# mainv5.net
KiCad netlist of a schematic drawn in EAGLE
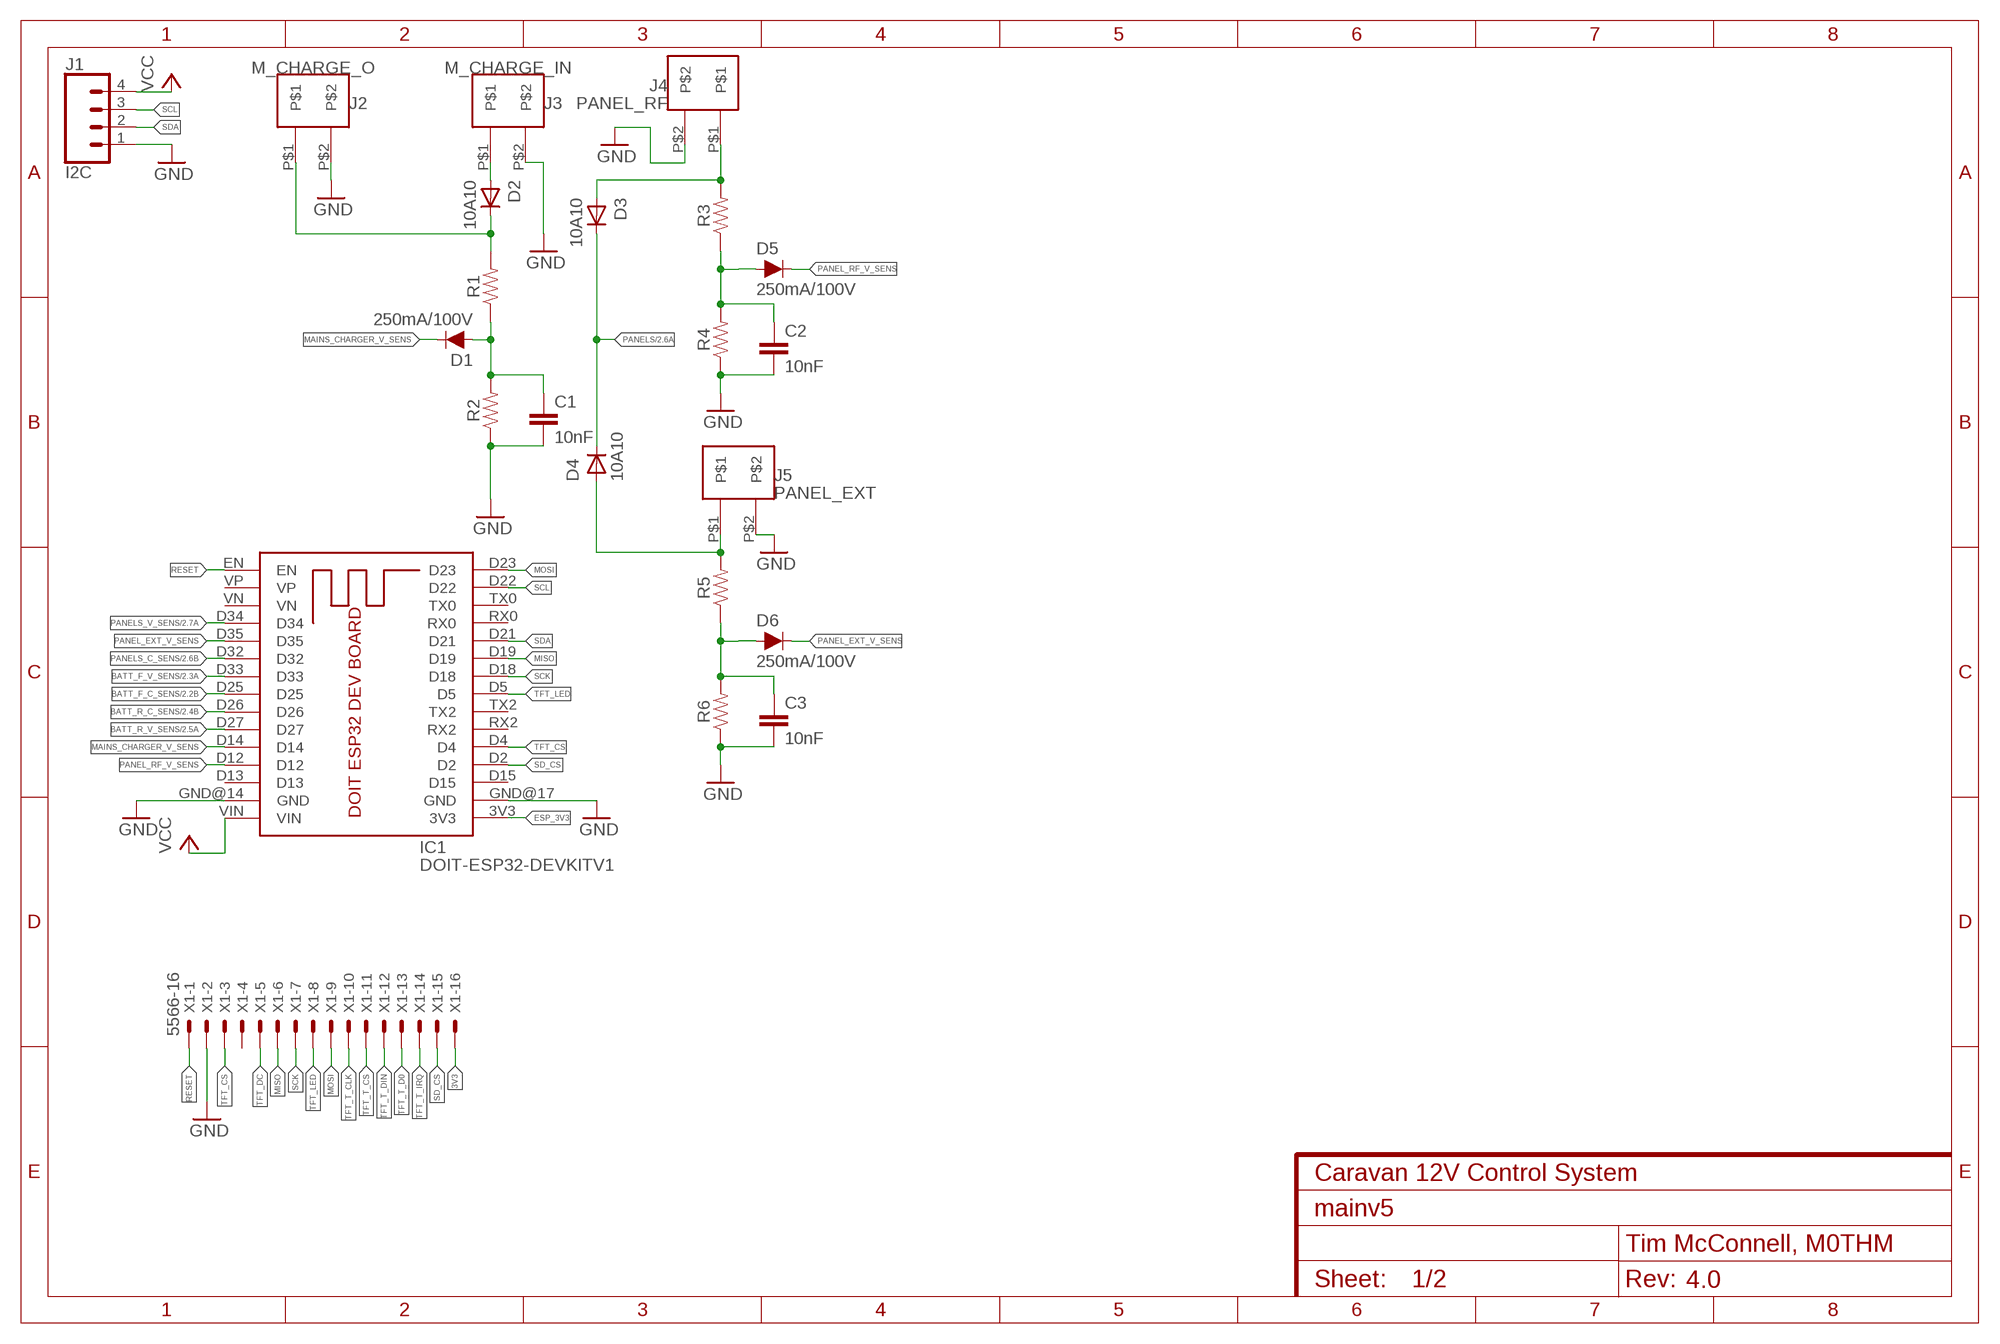
[diagram p0: schematic, sheet 1]
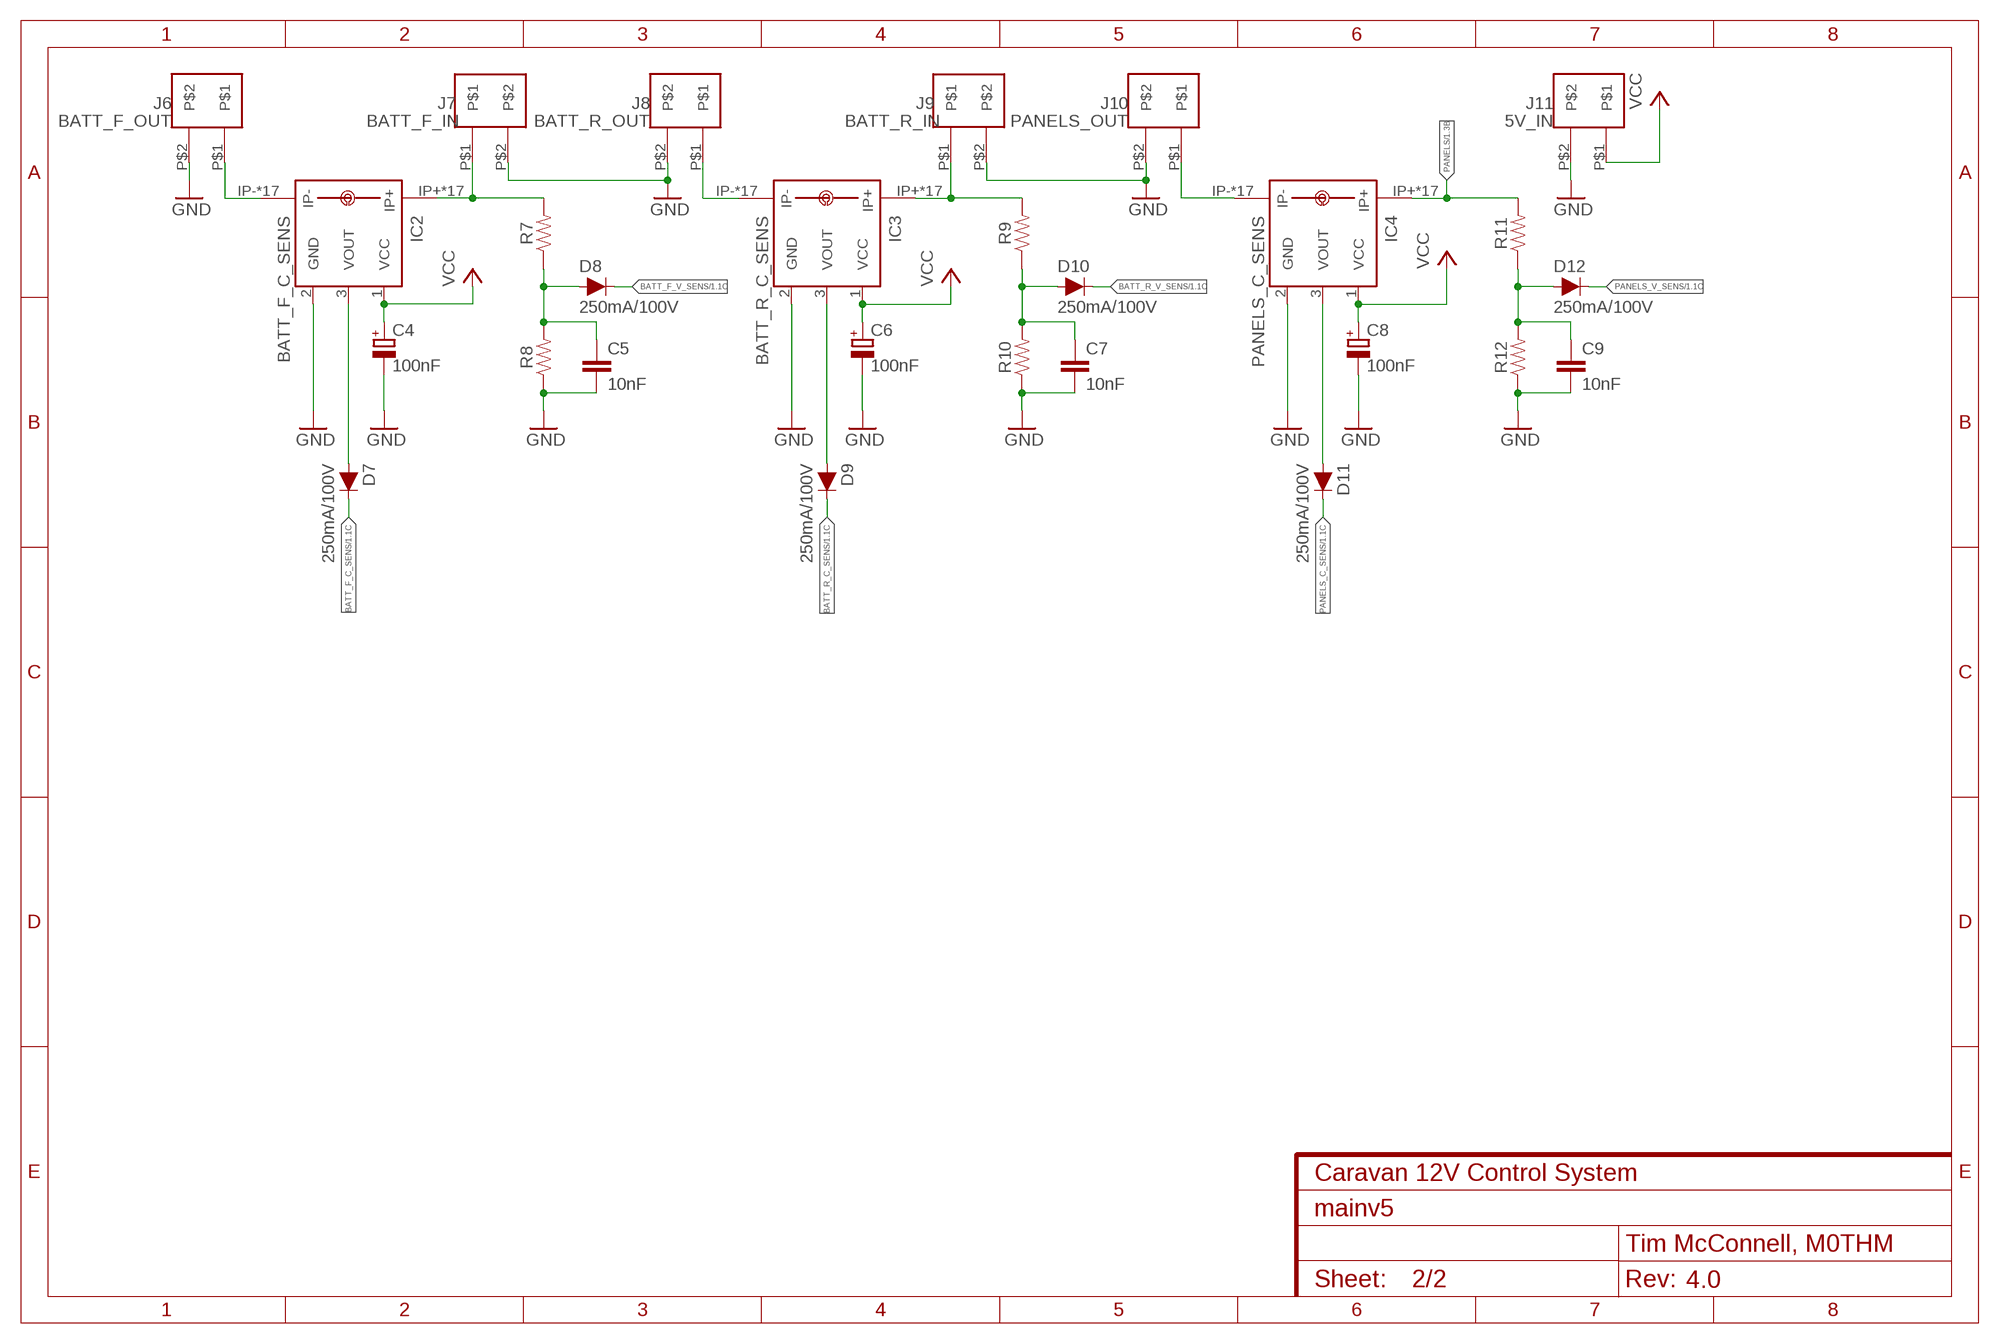
[diagram p1: schematic, sheet 2]

(export (version "E")
  (design (tool "Eeschema 10.0.6"))
  (components
    (comp (ref "C4")
      (value "100nF")
      (footprint "eagle-import:PANASONIC_E")
      (libsource (lib "eagle-import") (part "CPOL-EUE"))
    )
    (comp (ref "C5")
      (value "10nF")
      (footprint "eagle-import:0603")
      (libsource (lib "eagle-import") (part "10NF-0603-50V-10%"))
    )
    (comp (ref "C6")
      (value "100nF")
      (footprint "eagle-import:PANASONIC_E")
      (libsource (lib "eagle-import") (part "CPOL-EUE"))
    )
    (comp (ref "C7")
      (value "10nF")
      (footprint "eagle-import:0603")
      (libsource (lib "eagle-import") (part "10NF-0603-50V-10%"))
    )
    (comp (ref "C8")
      (value "100nF")
      (footprint "eagle-import:PANASONIC_E")
      (libsource (lib "eagle-import") (part "CPOL-EUE"))
    )
    (comp (ref "C9")
      (value "10nF")
      (footprint "eagle-import:0603")
      (libsource (lib "eagle-import") (part "10NF-0603-50V-10%"))
    )
    (comp (ref "D7")
      (value "250mA/100V")
      (footprint "eagle-import:SOD-323")
      (libsource (lib "eagle-import") (part "DIODE-BAS16J"))
    )
    (comp (ref "D8")
      (value "250mA/100V")
      (footprint "eagle-import:SOD-323")
      (libsource (lib "eagle-import") (part "DIODE-BAS16J"))
    )
    (comp (ref "D9")
      (value "250mA/100V")
      (footprint "eagle-import:SOD-323")
      (libsource (lib "eagle-import") (part "DIODE-BAS16J"))
    )
    (comp (ref "D10")
      (value "250mA/100V")
      (footprint "eagle-import:SOD-323")
      (libsource (lib "eagle-import") (part "DIODE-BAS16J"))
    )
    (comp (ref "D11")
      (value "250mA/100V")
      (footprint "eagle-import:SOD-323")
      (libsource (lib "eagle-import") (part "DIODE-BAS16J"))
    )
    (comp (ref "D12")
      (value "250mA/100V")
      (footprint "eagle-import:SOD-323")
      (libsource (lib "eagle-import") (part "DIODE-BAS16J"))
    )
    (comp (ref "IC2")
      (value "BATT_F_C_SENS")
      (footprint "eagle-import:CB-PFF")
      (fields (field (name "MPN") "ACS758ECB-200B-PFF-T"))
      (libsource (lib "eagle-import") (part "ACS758ECB-200B-PFF-T"))
    )
    (comp (ref "IC3")
      (value "BATT_R_C_SENS")
      (footprint "eagle-import:CB-PFF")
      (fields (field (name "MPN") "ACS758ECB-200B-PFF-T"))
      (libsource (lib "eagle-import") (part "ACS758ECB-200B-PFF-T"))
    )
    (comp (ref "IC4")
      (value "PANELS_C_SENS")
      (footprint "eagle-import:CB-PFF")
      (fields (field (name "MPN") "ACS758ECB-200B-PFF-T"))
      (libsource (lib "eagle-import") (part "ACS758ECB-200B-PFF-T"))
    )
    (comp (ref "J6")
      (value "BATT_F_OUT")
      (footprint "eagle-import:40A-2PIN")
      (libsource (lib "eagle-import") (part "40A-2PIN"))
    )
    (comp (ref "J7")
      (value "BATT_F_IN")
      (footprint "eagle-import:40A-2PIN")
      (libsource (lib "eagle-import") (part "40A-2PIN"))
    )
    (comp (ref "J8")
      (value "BATT_R_OUT")
      (footprint "eagle-import:40A-2PIN")
      (libsource (lib "eagle-import") (part "40A-2PIN"))
    )
    (comp (ref "J9")
      (value "BATT_R_IN")
      (footprint "eagle-import:40A-2PIN")
      (libsource (lib "eagle-import") (part "40A-2PIN"))
    )
    (comp (ref "J10")
      (value "PANELS_OUT")
      (footprint "eagle-import:40A-2PIN")
      (libsource (lib "eagle-import") (part "40A-2PIN"))
    )
    (comp (ref "J11")
      (value "5V_IN")
      (footprint "eagle-import:40A-2PIN")
      (libsource (lib "eagle-import") (part "40A-2PIN"))
    )
    (comp (ref "R7")
      (value "RESISTOR0805")
      (footprint "eagle-import:0805")
      (libsource (lib "eagle-import") (part "RESISTOR0805"))
    )
    (comp (ref "R8")
      (value "RESISTOR0805")
      (footprint "eagle-import:0805")
      (libsource (lib "eagle-import") (part "RESISTOR0805"))
    )
    (comp (ref "R9")
      (value "RESISTOR0805")
      (footprint "eagle-import:0805")
      (libsource (lib "eagle-import") (part "RESISTOR0805"))
    )
    (comp (ref "R10")
      (value "RESISTOR0805")
      (footprint "eagle-import:0805")
      (libsource (lib "eagle-import") (part "RESISTOR0805"))
    )
    (comp (ref "R11")
      (value "RESISTOR0805")
      (footprint "eagle-import:0805")
      (libsource (lib "eagle-import") (part "RESISTOR0805"))
    )
    (comp (ref "R12")
      (value "RESISTOR0805")
      (footprint "eagle-import:0805")
      (libsource (lib "eagle-import") (part "RESISTOR0805"))
    )
    (comp (ref "C1")
      (value "10nF")
      (footprint "eagle-import:0603")
      (libsource (lib "eagle-import") (part "10NF-0603-50V-10%"))
    )
    (comp (ref "C2")
      (value "10nF")
      (footprint "eagle-import:0603")
      (libsource (lib "eagle-import") (part "10NF-0603-50V-10%"))
    )
    (comp (ref "C3")
      (value "10nF")
      (footprint "eagle-import:0603")
      (libsource (lib "eagle-import") (part "10NF-0603-50V-10%"))
    )
    (comp (ref "D1")
      (value "250mA/100V")
      (footprint "eagle-import:SOD-323")
      (libsource (lib "eagle-import") (part "DIODE-BAS16J"))
    )
    (comp (ref "D2")
      (value "10A10")
      (footprint "eagle-import:AG")
      (libsource (lib "eagle-import") (part "10A10"))
    )
    (comp (ref "D3")
      (value "10A10")
      (footprint "eagle-import:AG")
      (libsource (lib "eagle-import") (part "10A10"))
    )
    (comp (ref "D4")
      (value "10A10")
      (footprint "eagle-import:AG")
      (libsource (lib "eagle-import") (part "10A10"))
    )
    (comp (ref "D5")
      (value "250mA/100V")
      (footprint "eagle-import:SOD-323")
      (libsource (lib "eagle-import") (part "DIODE-BAS16J"))
    )
    (comp (ref "D6")
      (value "250mA/100V")
      (footprint "eagle-import:SOD-323")
      (libsource (lib "eagle-import") (part "DIODE-BAS16J"))
    )
    (comp (ref "IC1")
      (value "DOIT-ESP32-DEVKITV1")
      (footprint "eagle-import:DOIT-ESP32-DEVKITV1")
      (libsource (lib "eagle-import") (part "DOIT-ESP32-DEVKITV1"))
    )
    (comp (ref "J1")
      (value "I2C")
      (footprint "eagle-import:MOLEX-1X4")
      (libsource (lib "eagle-import") (part "CONN_04POLAR"))
    )
    (comp (ref "J2")
      (value "M_CHARGE_O")
      (footprint "eagle-import:40A-2PIN")
      (libsource (lib "eagle-import") (part "40A-2PIN"))
    )
    (comp (ref "J3")
      (value "M_CHARGE_IN")
      (footprint "eagle-import:40A-2PIN")
      (libsource (lib "eagle-import") (part "40A-2PIN"))
    )
    (comp (ref "J4")
      (value "PANEL_RF")
      (footprint "eagle-import:40A-2PIN")
      (libsource (lib "eagle-import") (part "40A-2PIN"))
    )
    (comp (ref "J5")
      (value "PANEL_EXT")
      (footprint "eagle-import:40A-2PIN")
      (libsource (lib "eagle-import") (part "40A-2PIN"))
    )
    (comp (ref "R1")
      (value "RESISTOR0805")
      (footprint "eagle-import:0805")
      (libsource (lib "eagle-import") (part "RESISTOR0805"))
    )
    (comp (ref "R2")
      (value "RESISTOR0805")
      (footprint "eagle-import:0805")
      (libsource (lib "eagle-import") (part "RESISTOR0805"))
    )
    (comp (ref "R3")
      (value "RESISTOR0805")
      (footprint "eagle-import:0805")
      (libsource (lib "eagle-import") (part "RESISTOR0805"))
    )
    (comp (ref "R4")
      (value "RESISTOR0805")
      (footprint "eagle-import:0805")
      (libsource (lib "eagle-import") (part "RESISTOR0805"))
    )
    (comp (ref "R5")
      (value "RESISTOR0805")
      (footprint "eagle-import:0805")
      (libsource (lib "eagle-import") (part "RESISTOR0805"))
    )
    (comp (ref "R6")
      (value "RESISTOR0805")
      (footprint "eagle-import:0805")
      (libsource (lib "eagle-import") (part "RESISTOR0805"))
    )
    (comp (ref "X1")
      (value "5566-16")
      (footprint "eagle-import:5566-16")
      (fields (field (name "MF") "MOLEX"))
      (libsource (lib "eagle-import") (part "5566-16"))
    )
  )
  (nets
    (net (code "1") (name "3V3") (class "Default")
      (node (ref "X1") (pin "16") (pinfunction "S_16") (pintype "passive"))
    )
    (net (code "2") (name "BATT_F_C_SENS") (class "Default")
      (node (ref "D7") (pin "C") (pinfunction "C_C") (pintype "passive"))
      (node (ref "IC1") (pin "D25") (pinfunction "D25_D25") (pintype "bidirectional"))
    )
    (net (code "3") (name "BATT_F_V_SENS") (class "Default")
      (node (ref "D8") (pin "C") (pinfunction "C_C") (pintype "passive"))
      (node (ref "IC1") (pin "D33") (pinfunction "D33_D33") (pintype "bidirectional"))
    )
    (net (code "4") (name "BATT_R_C_SENS") (class "Default")
      (node (ref "D9") (pin "C") (pinfunction "C_C") (pintype "passive"))
      (node (ref "IC1") (pin "D26") (pinfunction "D26_D26") (pintype "bidirectional"))
    )
    (net (code "5") (name "BATT_R_V_SENS") (class "Default")
      (node (ref "D10") (pin "C") (pinfunction "C_C") (pintype "passive"))
      (node (ref "IC1") (pin "D27") (pinfunction "D27_D27") (pintype "bidirectional"))
    )
    (net (code "6") (name "ESP_3V3") (class "Default")
      (node (ref "IC1") (pin "3V3") (pinfunction "3V3_3V3") (pintype "power_in"))
    )
    (net (code "7") (name "GND") (class "Default")
      (node (ref "C1") (pin "2") (pinfunction "2_2") (pintype "passive"))
      (node (ref "C2") (pin "2") (pinfunction "2_2") (pintype "passive"))
      (node (ref "C3") (pin "2") (pinfunction "2_2") (pintype "passive"))
      (node (ref "C4") (pin "-") (pinfunction "-_-") (pintype "passive"))
      (node (ref "C5") (pin "2") (pinfunction "2_2") (pintype "passive"))
      (node (ref "C6") (pin "-") (pinfunction "-_-") (pintype "passive"))
      (node (ref "C7") (pin "2") (pinfunction "2_2") (pintype "passive"))
      (node (ref "C8") (pin "-") (pinfunction "-_-") (pintype "passive"))
      (node (ref "C9") (pin "2") (pinfunction "2_2") (pintype "passive"))
      (node (ref "IC1") (pin "GND@14") (pinfunction "GND_GND@14") (pintype "power_in"))
      (node (ref "IC1") (pin "GND@17") (pinfunction "GND_GND@17") (pintype "power_in"))
      (node (ref "IC2") (pin "2") (pinfunction "GND_2") (pintype "power_in"))
      (node (ref "IC3") (pin "2") (pinfunction "GND_2") (pintype "power_in"))
      (node (ref "IC4") (pin "2") (pinfunction "GND_2") (pintype "power_in"))
      (node (ref "J1") (pin "1") (pinfunction "1_1") (pintype "passive"))
      (node (ref "J10") (pin "P$2") (pinfunction "P$2_P$2") (pintype "bidirectional"))
      (node (ref "J11") (pin "P$2") (pinfunction "P$2_P$2") (pintype "bidirectional"))
      (node (ref "J2") (pin "P$2") (pinfunction "P$2_P$2") (pintype "bidirectional"))
      (node (ref "J3") (pin "P$2") (pinfunction "P$2_P$2") (pintype "bidirectional"))
      (node (ref "J4") (pin "P$2") (pinfunction "P$2_P$2") (pintype "bidirectional"))
      (node (ref "J5") (pin "P$2") (pinfunction "P$2_P$2") (pintype "bidirectional"))
      (node (ref "J6") (pin "P$2") (pinfunction "P$2_P$2") (pintype "bidirectional"))
      (node (ref "J7") (pin "P$2") (pinfunction "P$2_P$2") (pintype "bidirectional"))
      (node (ref "J8") (pin "P$2") (pinfunction "P$2_P$2") (pintype "bidirectional"))
      (node (ref "J9") (pin "P$2") (pinfunction "P$2_P$2") (pintype "bidirectional"))
      (node (ref "R10") (pin "1") (pinfunction "1_1") (pintype "passive"))
      (node (ref "R12") (pin "1") (pinfunction "1_1") (pintype "passive"))
      (node (ref "R2") (pin "1") (pinfunction "1_1") (pintype "passive"))
      (node (ref "R4") (pin "1") (pinfunction "1_1") (pintype "passive"))
      (node (ref "R6") (pin "1") (pinfunction "1_1") (pintype "passive"))
      (node (ref "R8") (pin "1") (pinfunction "1_1") (pintype "passive"))
      (node (ref "X1") (pin "2") (pinfunction "S_2") (pintype "passive"))
    )
    (net (code "8") (name "MAINS_CHARGER_V_SENS") (class "Default")
      (node (ref "D1") (pin "C") (pinfunction "C_C") (pintype "passive"))
      (node (ref "IC1") (pin "D14") (pinfunction "D14_D14") (pintype "bidirectional"))
    )
    (net (code "9") (name "MISO") (class "Default")
      (node (ref "IC1") (pin "D19") (pinfunction "D19_D19") (pintype "bidirectional"))
      (node (ref "X1") (pin "6") (pinfunction "S_6") (pintype "passive"))
    )
    (net (code "10") (name "MOSI") (class "Default")
      (node (ref "IC1") (pin "D23") (pinfunction "D23_D23") (pintype "bidirectional"))
      (node (ref "X1") (pin "9") (pinfunction "S_9") (pintype "passive"))
    )
    (net (code "11") (name "Net-(C1-Pad1)") (class "Default")
      (node (ref "C1") (pin "1") (pinfunction "1_1") (pintype "passive"))
      (node (ref "D1") (pin "A") (pinfunction "A_A") (pintype "passive"))
      (node (ref "R1") (pin "1") (pinfunction "1_1") (pintype "passive"))
      (node (ref "R2") (pin "2") (pinfunction "2_2") (pintype "passive"))
    )
    (net (code "12") (name "Net-(C2-Pad1)") (class "Default")
      (node (ref "C2") (pin "1") (pinfunction "1_1") (pintype "passive"))
      (node (ref "D5") (pin "A") (pinfunction "A_A") (pintype "passive"))
      (node (ref "R3") (pin "1") (pinfunction "1_1") (pintype "passive"))
      (node (ref "R4") (pin "2") (pinfunction "2_2") (pintype "passive"))
    )
    (net (code "13") (name "Net-(C3-Pad1)") (class "Default")
      (node (ref "C3") (pin "1") (pinfunction "1_1") (pintype "passive"))
      (node (ref "D6") (pin "A") (pinfunction "A_A") (pintype "passive"))
      (node (ref "R5") (pin "1") (pinfunction "1_1") (pintype "passive"))
      (node (ref "R6") (pin "2") (pinfunction "2_2") (pintype "passive"))
    )
    (net (code "14") (name "Net-(C5-Pad1)") (class "Default")
      (node (ref "C5") (pin "1") (pinfunction "1_1") (pintype "passive"))
      (node (ref "D8") (pin "A") (pinfunction "A_A") (pintype "passive"))
      (node (ref "R7") (pin "1") (pinfunction "1_1") (pintype "passive"))
      (node (ref "R8") (pin "2") (pinfunction "2_2") (pintype "passive"))
    )
    (net (code "15") (name "Net-(C7-Pad1)") (class "Default")
      (node (ref "C7") (pin "1") (pinfunction "1_1") (pintype "passive"))
      (node (ref "D10") (pin "A") (pinfunction "A_A") (pintype "passive"))
      (node (ref "R10") (pin "2") (pinfunction "2_2") (pintype "passive"))
      (node (ref "R9") (pin "1") (pinfunction "1_1") (pintype "passive"))
    )
    (net (code "16") (name "Net-(C9-Pad1)") (class "Default")
      (node (ref "C9") (pin "1") (pinfunction "1_1") (pintype "passive"))
      (node (ref "D12") (pin "A") (pinfunction "A_A") (pintype "passive"))
      (node (ref "R11") (pin "1") (pinfunction "1_1") (pintype "passive"))
      (node (ref "R12") (pin "2") (pinfunction "2_2") (pintype "passive"))
    )
    (net (code "17") (name "Net-(D2-PadA)") (class "Default")
      (node (ref "D2") (pin "A") (pinfunction "A_A") (pintype "passive"))
      (node (ref "J3") (pin "P$1") (pinfunction "P$1_P$1") (pintype "bidirectional"))
    )
    (net (code "18") (name "Net-(D2-PadC)") (class "Default")
      (node (ref "D2") (pin "C") (pinfunction "C_C") (pintype "passive"))
      (node (ref "J2") (pin "P$1") (pinfunction "P$1_P$1") (pintype "bidirectional"))
      (node (ref "R1") (pin "2") (pinfunction "2_2") (pintype "passive"))
    )
    (net (code "19") (name "Net-(D3-PadA)") (class "Default")
      (node (ref "D3") (pin "A") (pinfunction "A_A") (pintype "passive"))
      (node (ref "J4") (pin "P$1") (pinfunction "P$1_P$1") (pintype "bidirectional"))
      (node (ref "R3") (pin "2") (pinfunction "2_2") (pintype "passive"))
    )
    (net (code "20") (name "Net-(D4-PadA)") (class "Default")
      (node (ref "D4") (pin "A") (pinfunction "A_A") (pintype "passive"))
      (node (ref "J5") (pin "P$1") (pinfunction "P$1_P$1") (pintype "bidirectional"))
      (node (ref "R5") (pin "2") (pinfunction "2_2") (pintype "passive"))
    )
    (net (code "21") (name "Net-(IC2-IP+-PadIP+@10)") (class "Default")
      (node (ref "IC2") (pin "IP+") (pinfunction "IP+_IP+") (pintype "passive"))
      (node (ref "IC2") (pin "IP+@10") (pinfunction "IP+_IP+@10") (pintype "passive"))
      (node (ref "IC2") (pin "IP+@11") (pinfunction "IP+_IP+@11") (pintype "passive"))
      (node (ref "IC2") (pin "IP+@12") (pinfunction "IP+_IP+@12") (pintype "passive"))
      (node (ref "IC2") (pin "IP+@13") (pinfunction "IP+_IP+@13") (pintype "passive"))
      (node (ref "IC2") (pin "IP+@14") (pinfunction "IP+_IP+@14") (pintype "passive"))
      (node (ref "IC2") (pin "IP+@15") (pinfunction "IP+_IP+@15") (pintype "passive"))
      (node (ref "IC2") (pin "IP+@16") (pinfunction "IP+_IP+@16") (pintype "passive"))
      (node (ref "IC2") (pin "IP+@17") (pinfunction "IP+_IP+@17") (pintype "passive"))
      (node (ref "IC2") (pin "IP+@2") (pinfunction "IP+_IP+@2") (pintype "passive"))
      (node (ref "IC2") (pin "IP+@3") (pinfunction "IP+_IP+@3") (pintype "passive"))
      (node (ref "IC2") (pin "IP+@4") (pinfunction "IP+_IP+@4") (pintype "passive"))
      (node (ref "IC2") (pin "IP+@5") (pinfunction "IP+_IP+@5") (pintype "passive"))
      (node (ref "IC2") (pin "IP+@6") (pinfunction "IP+_IP+@6") (pintype "passive"))
      (node (ref "IC2") (pin "IP+@7") (pinfunction "IP+_IP+@7") (pintype "passive"))
      (node (ref "IC2") (pin "IP+@8") (pinfunction "IP+_IP+@8") (pintype "passive"))
      (node (ref "IC2") (pin "IP+@9") (pinfunction "IP+_IP+@9") (pintype "passive"))
      (node (ref "J7") (pin "P$1") (pinfunction "P$1_P$1") (pintype "bidirectional"))
      (node (ref "R7") (pin "2") (pinfunction "2_2") (pintype "passive"))
    )
    (net (code "22") (name "Net-(IC2-IP--PadIP-@10)") (class "Default")
      (node (ref "IC2") (pin "IP-") (pinfunction "IP-_IP-") (pintype "passive"))
      (node (ref "IC2") (pin "IP-@10") (pinfunction "IP-_IP-@10") (pintype "passive"))
      (node (ref "IC2") (pin "IP-@11") (pinfunction "IP-_IP-@11") (pintype "passive"))
      (node (ref "IC2") (pin "IP-@12") (pinfunction "IP-_IP-@12") (pintype "passive"))
      (node (ref "IC2") (pin "IP-@13") (pinfunction "IP-_IP-@13") (pintype "passive"))
      (node (ref "IC2") (pin "IP-@14") (pinfunction "IP-_IP-@14") (pintype "passive"))
      (node (ref "IC2") (pin "IP-@15") (pinfunction "IP-_IP-@15") (pintype "passive"))
      (node (ref "IC2") (pin "IP-@16") (pinfunction "IP-_IP-@16") (pintype "passive"))
      (node (ref "IC2") (pin "IP-@17") (pinfunction "IP-_IP-@17") (pintype "passive"))
      (node (ref "IC2") (pin "IP-@2") (pinfunction "IP-_IP-@2") (pintype "passive"))
      (node (ref "IC2") (pin "IP-@3") (pinfunction "IP-_IP-@3") (pintype "passive"))
      (node (ref "IC2") (pin "IP-@4") (pinfunction "IP-_IP-@4") (pintype "passive"))
      (node (ref "IC2") (pin "IP-@5") (pinfunction "IP-_IP-@5") (pintype "passive"))
      (node (ref "IC2") (pin "IP-@6") (pinfunction "IP-_IP-@6") (pintype "passive"))
      (node (ref "IC2") (pin "IP-@7") (pinfunction "IP-_IP-@7") (pintype "passive"))
      (node (ref "IC2") (pin "IP-@8") (pinfunction "IP-_IP-@8") (pintype "passive"))
      (node (ref "IC2") (pin "IP-@9") (pinfunction "IP-_IP-@9") (pintype "passive"))
      (node (ref "J6") (pin "P$1") (pinfunction "P$1_P$1") (pintype "bidirectional"))
    )
    (net (code "23") (name "Net-(IC2-VOUT)") (class "Default")
      (node (ref "D7") (pin "A") (pinfunction "A_A") (pintype "passive"))
      (node (ref "IC2") (pin "3") (pinfunction "VOUT_3") (pintype "output"))
    )
    (net (code "24") (name "Net-(IC3-IP+-PadIP+@10)") (class "Default")
      (node (ref "IC3") (pin "IP+") (pinfunction "IP+_IP+") (pintype "passive"))
      (node (ref "IC3") (pin "IP+@10") (pinfunction "IP+_IP+@10") (pintype "passive"))
      (node (ref "IC3") (pin "IP+@11") (pinfunction "IP+_IP+@11") (pintype "passive"))
      (node (ref "IC3") (pin "IP+@12") (pinfunction "IP+_IP+@12") (pintype "passive"))
      (node (ref "IC3") (pin "IP+@13") (pinfunction "IP+_IP+@13") (pintype "passive"))
      (node (ref "IC3") (pin "IP+@14") (pinfunction "IP+_IP+@14") (pintype "passive"))
      (node (ref "IC3") (pin "IP+@15") (pinfunction "IP+_IP+@15") (pintype "passive"))
      (node (ref "IC3") (pin "IP+@16") (pinfunction "IP+_IP+@16") (pintype "passive"))
      (node (ref "IC3") (pin "IP+@17") (pinfunction "IP+_IP+@17") (pintype "passive"))
      (node (ref "IC3") (pin "IP+@2") (pinfunction "IP+_IP+@2") (pintype "passive"))
      (node (ref "IC3") (pin "IP+@3") (pinfunction "IP+_IP+@3") (pintype "passive"))
      (node (ref "IC3") (pin "IP+@4") (pinfunction "IP+_IP+@4") (pintype "passive"))
      (node (ref "IC3") (pin "IP+@5") (pinfunction "IP+_IP+@5") (pintype "passive"))
      (node (ref "IC3") (pin "IP+@6") (pinfunction "IP+_IP+@6") (pintype "passive"))
      (node (ref "IC3") (pin "IP+@7") (pinfunction "IP+_IP+@7") (pintype "passive"))
      (node (ref "IC3") (pin "IP+@8") (pinfunction "IP+_IP+@8") (pintype "passive"))
      (node (ref "IC3") (pin "IP+@9") (pinfunction "IP+_IP+@9") (pintype "passive"))
      (node (ref "J9") (pin "P$1") (pinfunction "P$1_P$1") (pintype "bidirectional"))
      (node (ref "R9") (pin "2") (pinfunction "2_2") (pintype "passive"))
    )
    (net (code "25") (name "Net-(IC3-IP--PadIP-@10)") (class "Default")
      (node (ref "IC3") (pin "IP-") (pinfunction "IP-_IP-") (pintype "passive"))
      (node (ref "IC3") (pin "IP-@10") (pinfunction "IP-_IP-@10") (pintype "passive"))
      (node (ref "IC3") (pin "IP-@11") (pinfunction "IP-_IP-@11") (pintype "passive"))
      (node (ref "IC3") (pin "IP-@12") (pinfunction "IP-_IP-@12") (pintype "passive"))
      (node (ref "IC3") (pin "IP-@13") (pinfunction "IP-_IP-@13") (pintype "passive"))
      (node (ref "IC3") (pin "IP-@14") (pinfunction "IP-_IP-@14") (pintype "passive"))
      (node (ref "IC3") (pin "IP-@15") (pinfunction "IP-_IP-@15") (pintype "passive"))
      (node (ref "IC3") (pin "IP-@16") (pinfunction "IP-_IP-@16") (pintype "passive"))
      (node (ref "IC3") (pin "IP-@17") (pinfunction "IP-_IP-@17") (pintype "passive"))
      (node (ref "IC3") (pin "IP-@2") (pinfunction "IP-_IP-@2") (pintype "passive"))
      (node (ref "IC3") (pin "IP-@3") (pinfunction "IP-_IP-@3") (pintype "passive"))
      (node (ref "IC3") (pin "IP-@4") (pinfunction "IP-_IP-@4") (pintype "passive"))
      (node (ref "IC3") (pin "IP-@5") (pinfunction "IP-_IP-@5") (pintype "passive"))
      (node (ref "IC3") (pin "IP-@6") (pinfunction "IP-_IP-@6") (pintype "passive"))
      (node (ref "IC3") (pin "IP-@7") (pinfunction "IP-_IP-@7") (pintype "passive"))
      (node (ref "IC3") (pin "IP-@8") (pinfunction "IP-_IP-@8") (pintype "passive"))
      (node (ref "IC3") (pin "IP-@9") (pinfunction "IP-_IP-@9") (pintype "passive"))
      (node (ref "J8") (pin "P$1") (pinfunction "P$1_P$1") (pintype "bidirectional"))
    )
    (net (code "26") (name "Net-(IC3-VOUT)") (class "Default")
      (node (ref "D9") (pin "A") (pinfunction "A_A") (pintype "passive"))
      (node (ref "IC3") (pin "3") (pinfunction "VOUT_3") (pintype "output"))
    )
    (net (code "27") (name "Net-(IC4-IP--PadIP-@10)") (class "Default")
      (node (ref "IC4") (pin "IP-") (pinfunction "IP-_IP-") (pintype "passive"))
      (node (ref "IC4") (pin "IP-@10") (pinfunction "IP-_IP-@10") (pintype "passive"))
      (node (ref "IC4") (pin "IP-@11") (pinfunction "IP-_IP-@11") (pintype "passive"))
      (node (ref "IC4") (pin "IP-@12") (pinfunction "IP-_IP-@12") (pintype "passive"))
      (node (ref "IC4") (pin "IP-@13") (pinfunction "IP-_IP-@13") (pintype "passive"))
      (node (ref "IC4") (pin "IP-@14") (pinfunction "IP-_IP-@14") (pintype "passive"))
      (node (ref "IC4") (pin "IP-@15") (pinfunction "IP-_IP-@15") (pintype "passive"))
      (node (ref "IC4") (pin "IP-@16") (pinfunction "IP-_IP-@16") (pintype "passive"))
      (node (ref "IC4") (pin "IP-@17") (pinfunction "IP-_IP-@17") (pintype "passive"))
      (node (ref "IC4") (pin "IP-@2") (pinfunction "IP-_IP-@2") (pintype "passive"))
      (node (ref "IC4") (pin "IP-@3") (pinfunction "IP-_IP-@3") (pintype "passive"))
      (node (ref "IC4") (pin "IP-@4") (pinfunction "IP-_IP-@4") (pintype "passive"))
      (node (ref "IC4") (pin "IP-@5") (pinfunction "IP-_IP-@5") (pintype "passive"))
      (node (ref "IC4") (pin "IP-@6") (pinfunction "IP-_IP-@6") (pintype "passive"))
      (node (ref "IC4") (pin "IP-@7") (pinfunction "IP-_IP-@7") (pintype "passive"))
      (node (ref "IC4") (pin "IP-@8") (pinfunction "IP-_IP-@8") (pintype "passive"))
      (node (ref "IC4") (pin "IP-@9") (pinfunction "IP-_IP-@9") (pintype "passive"))
      (node (ref "J10") (pin "P$1") (pinfunction "P$1_P$1") (pintype "bidirectional"))
    )
    (net (code "28") (name "Net-(IC4-VOUT)") (class "Default")
      (node (ref "D11") (pin "A") (pinfunction "A_A") (pintype "passive"))
      (node (ref "IC4") (pin "3") (pinfunction "VOUT_3") (pintype "output"))
    )
    (net (code "29") (name "PANELS") (class "Default")
      (node (ref "D3") (pin "C") (pinfunction "C_C") (pintype "passive"))
      (node (ref "D4") (pin "C") (pinfunction "C_C") (pintype "passive"))
      (node (ref "IC4") (pin "IP+") (pinfunction "IP+_IP+") (pintype "passive"))
      (node (ref "IC4") (pin "IP+@10") (pinfunction "IP+_IP+@10") (pintype "passive"))
      (node (ref "IC4") (pin "IP+@11") (pinfunction "IP+_IP+@11") (pintype "passive"))
      (node (ref "IC4") (pin "IP+@12") (pinfunction "IP+_IP+@12") (pintype "passive"))
      (node (ref "IC4") (pin "IP+@13") (pinfunction "IP+_IP+@13") (pintype "passive"))
      (node (ref "IC4") (pin "IP+@14") (pinfunction "IP+_IP+@14") (pintype "passive"))
      (node (ref "IC4") (pin "IP+@15") (pinfunction "IP+_IP+@15") (pintype "passive"))
      (node (ref "IC4") (pin "IP+@16") (pinfunction "IP+_IP+@16") (pintype "passive"))
      (node (ref "IC4") (pin "IP+@17") (pinfunction "IP+_IP+@17") (pintype "passive"))
      (node (ref "IC4") (pin "IP+@2") (pinfunction "IP+_IP+@2") (pintype "passive"))
      (node (ref "IC4") (pin "IP+@3") (pinfunction "IP+_IP+@3") (pintype "passive"))
      (node (ref "IC4") (pin "IP+@4") (pinfunction "IP+_IP+@4") (pintype "passive"))
      (node (ref "IC4") (pin "IP+@5") (pinfunction "IP+_IP+@5") (pintype "passive"))
      (node (ref "IC4") (pin "IP+@6") (pinfunction "IP+_IP+@6") (pintype "passive"))
      (node (ref "IC4") (pin "IP+@7") (pinfunction "IP+_IP+@7") (pintype "passive"))
      (node (ref "IC4") (pin "IP+@8") (pinfunction "IP+_IP+@8") (pintype "passive"))
      (node (ref "IC4") (pin "IP+@9") (pinfunction "IP+_IP+@9") (pintype "passive"))
      (node (ref "R11") (pin "2") (pinfunction "2_2") (pintype "passive"))
    )
    (net (code "30") (name "PANELS_C_SENS") (class "Default")
      (node (ref "D11") (pin "C") (pinfunction "C_C") (pintype "passive"))
      (node (ref "IC1") (pin "D32") (pinfunction "D32_D32") (pintype "bidirectional"))
    )
    (net (code "31") (name "PANELS_V_SENS") (class "Default")
      (node (ref "D12") (pin "C") (pinfunction "C_C") (pintype "passive"))
      (node (ref "IC1") (pin "D34") (pinfunction "D34_D34") (pintype "bidirectional"))
    )
    (net (code "32") (name "PANEL_EXT_V_SENS") (class "Default")
      (node (ref "D6") (pin "C") (pinfunction "C_C") (pintype "passive"))
      (node (ref "IC1") (pin "D35") (pinfunction "D35_D35") (pintype "bidirectional"))
    )
    (net (code "33") (name "PANEL_RF_V_SENS") (class "Default")
      (node (ref "D5") (pin "C") (pinfunction "C_C") (pintype "passive"))
      (node (ref "IC1") (pin "D12") (pinfunction "D12_D12") (pintype "bidirectional"))
    )
    (net (code "34") (name "RESET") (class "Default")
      (node (ref "IC1") (pin "EN") (pinfunction "EN_EN") (pintype "bidirectional"))
      (node (ref "X1") (pin "1") (pinfunction "S_1") (pintype "passive"))
    )
    (net (code "35") (name "SCK") (class "Default")
      (node (ref "IC1") (pin "D18") (pinfunction "D18_D18") (pintype "bidirectional"))
      (node (ref "X1") (pin "7") (pinfunction "S_7") (pintype "passive"))
    )
    (net (code "36") (name "SCL") (class "Default")
      (node (ref "IC1") (pin "D22") (pinfunction "D22_D22") (pintype "bidirectional"))
      (node (ref "J1") (pin "3") (pinfunction "3_3") (pintype "passive"))
    )
    (net (code "37") (name "SDA") (class "Default")
      (node (ref "IC1") (pin "D21") (pinfunction "D21_D21") (pintype "bidirectional"))
      (node (ref "J1") (pin "2") (pinfunction "2_2") (pintype "passive"))
    )
    (net (code "38") (name "SD_CS") (class "Default")
      (node (ref "IC1") (pin "D2") (pinfunction "D2_D2") (pintype "bidirectional"))
      (node (ref "X1") (pin "15") (pinfunction "S_15") (pintype "passive"))
    )
    (net (code "39") (name "TFT_CS") (class "Default")
      (node (ref "IC1") (pin "D4") (pinfunction "D4_D4") (pintype "bidirectional"))
      (node (ref "X1") (pin "3") (pinfunction "S_3") (pintype "passive"))
    )
    (net (code "40") (name "TFT_DC") (class "Default")
      (node (ref "X1") (pin "5") (pinfunction "S_5") (pintype "passive"))
    )
    (net (code "41") (name "TFT_LED") (class "Default")
      (node (ref "IC1") (pin "D5") (pinfunction "D5_D5") (pintype "bidirectional"))
      (node (ref "X1") (pin "8") (pinfunction "S_8") (pintype "passive"))
    )
    (net (code "42") (name "TFT_T_CLK") (class "Default")
      (node (ref "X1") (pin "10") (pinfunction "S_10") (pintype "passive"))
    )
    (net (code "43") (name "TFT_T_CS") (class "Default")
      (node (ref "X1") (pin "11") (pinfunction "S_11") (pintype "passive"))
    )
    (net (code "44") (name "TFT_T_D0") (class "Default")
      (node (ref "X1") (pin "13") (pinfunction "S_13") (pintype "passive"))
    )
    (net (code "45") (name "TFT_T_DIN") (class "Default")
      (node (ref "X1") (pin "12") (pinfunction "S_12") (pintype "passive"))
    )
    (net (code "46") (name "TFT_T_IRQ") (class "Default")
      (node (ref "X1") (pin "14") (pinfunction "S_14") (pintype "passive"))
    )
    (net (code "47") (name "VCC") (class "Default")
      (node (ref "C4") (pin "+") (pinfunction "+_+") (pintype "passive"))
      (node (ref "C6") (pin "+") (pinfunction "+_+") (pintype "passive"))
      (node (ref "C8") (pin "+") (pinfunction "+_+") (pintype "passive"))
      (node (ref "IC1") (pin "VIN") (pinfunction "VIN_VIN") (pintype "power_in"))
      (node (ref "IC2") (pin "1") (pinfunction "VCC_1") (pintype "power_in"))
      (node (ref "IC3") (pin "1") (pinfunction "VCC_1") (pintype "power_in"))
      (node (ref "IC4") (pin "1") (pinfunction "VCC_1") (pintype "power_in"))
      (node (ref "J1") (pin "4") (pinfunction "4_4") (pintype "passive"))
      (node (ref "J11") (pin "P$1") (pinfunction "P$1_P$1") (pintype "bidirectional"))
    )
    (net (code "48") (name "unconnected-(IC1-PadD13)") (class "Default")
      (node (ref "IC1") (pin "D13") (pinfunction "D13_D13") (pintype "bidirectional"))
    )
    (net (code "49") (name "unconnected-(IC1-PadD15)") (class "Default")
      (node (ref "IC1") (pin "D15") (pinfunction "D15_D15") (pintype "bidirectional"))
    )
    (net (code "50") (name "unconnected-(IC1-PadRX0)") (class "Default")
      (node (ref "IC1") (pin "RX0") (pinfunction "RX0_RX0") (pintype "bidirectional"))
    )
    (net (code "51") (name "unconnected-(IC1-PadRX2)") (class "Default")
      (node (ref "IC1") (pin "RX2") (pinfunction "RX2_RX2") (pintype "bidirectional"))
    )
    (net (code "52") (name "unconnected-(IC1-PadTX0)") (class "Default")
      (node (ref "IC1") (pin "TX0") (pinfunction "TX0_TX0") (pintype "bidirectional"))
    )
    (net (code "53") (name "unconnected-(IC1-PadTX2)") (class "Default")
      (node (ref "IC1") (pin "TX2") (pinfunction "TX2_TX2") (pintype "bidirectional"))
    )
    (net (code "54") (name "unconnected-(IC1-PadVN)") (class "Default")
      (node (ref "IC1") (pin "VN") (pinfunction "VN_VN") (pintype "bidirectional"))
    )
    (net (code "55") (name "unconnected-(IC1-PadVP)") (class "Default")
      (node (ref "IC1") (pin "VP") (pinfunction "VP_VP") (pintype "bidirectional"))
    )
    (net (code "56") (name "unconnected-(X1K-S-Pad4)") (class "Default")
      (node (ref "X1") (pin "4") (pinfunction "S_4") (pintype "passive"))
    )
  )
)
